# 20_-CONNECT_CONNECTORS.net
KiCad netlist of a schematic drawn in Altium Designer
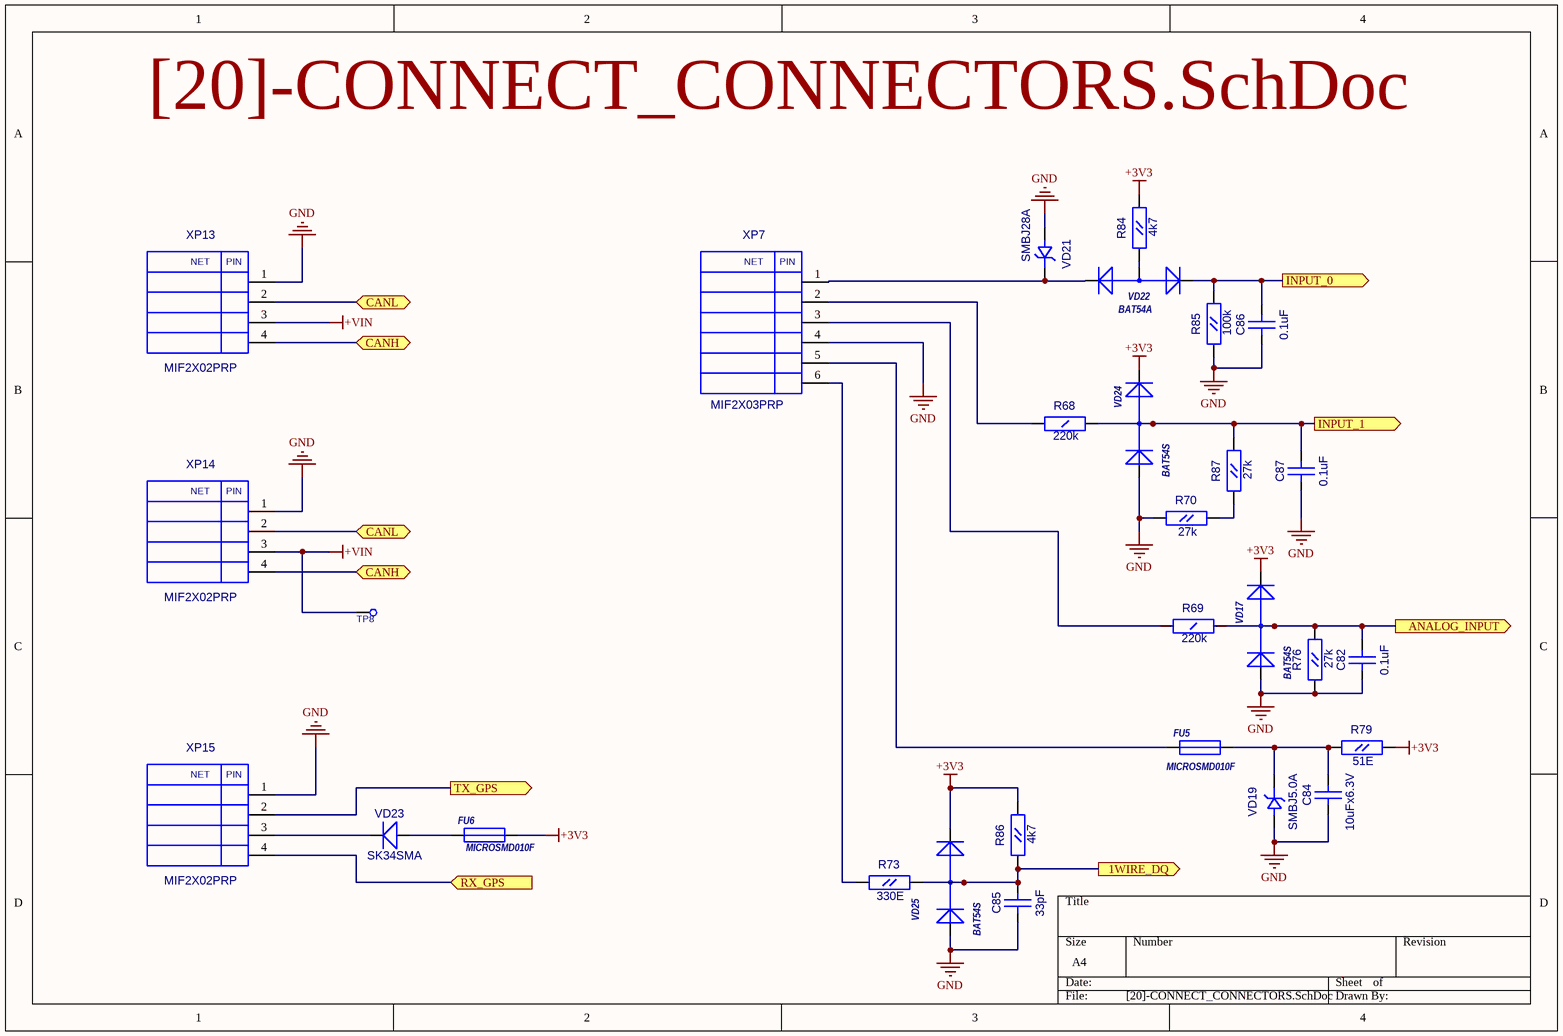
[diagram p0: [20]-CONNECT_CONNECTORS.SchDoc]

(export (version "E")
  (design (tool "Eeschema 10.0.6"))
  (components
    (comp (ref "C82")
      (value "0.1uF")
      (footprint "CC0603")
      (description "CC0603")
      (libsource (lib "gprs_modem_2") (part "CC0603"))
    )
    (comp (ref "C84")
      (value "10uFx6.3V")
      (footprint "CC0805")
      (description "CC0805")
      (libsource (lib "fizik_lib") (part "CC0805"))
    )
    (comp (ref "C85")
      (value "33pF")
      (footprint "CC0603")
      (description "CC0603")
      (libsource (lib "fizik_lib (1)") (part "CC0603"))
    )
    (comp (ref "C86")
      (value "0.1uF")
      (footprint "CC0603")
      (description "CC0603")
      (libsource (lib "fizik_lib") (part "CC0603"))
    )
    (comp (ref "C87")
      (value "0.1uF")
      (footprint "CC0603")
      (description "CC0603")
      (libsource (lib "gprs_modem_2") (part "CC0603"))
    )
    (comp (ref "FU5")
      (value "MICROSMD010F")
      (footprint "RC1210")
      (description "MICROSMD")
      (libsource (lib "fizik_lib (1)") (part "MICROSMD"))
    )
    (comp (ref "FU6")
      (value "MICROSMD010F")
      (footprint "RC1210")
      (description "MICROSMD")
      (libsource (lib "fizik_lib") (part "MICROSMD"))
    )
    (comp (ref "R68")
      (value "220k")
      (footprint "RC1206")
      (description "RC1206")
      (libsource (lib "fizik_lib") (part "RC1206"))
    )
    (comp (ref "R69")
      (value "220k")
      (footprint "RC1206")
      (description "RC1206")
      (libsource (lib "fizik_lib") (part "RC1206"))
    )
    (comp (ref "R70")
      (value "27k")
      (footprint "RC0603")
      (description "RC0603")
      (libsource (lib "fizik_lib") (part "RC0603"))
    )
    (comp (ref "R73")
      (value "330E")
      (footprint "RC0603")
      (description "RC0603")
      (libsource (lib "fizik_lib (1)") (part "RC0603"))
    )
    (comp (ref "R76")
      (value "27k")
      (footprint "RC0603")
      (description "RC0603")
      (libsource (lib "gprs_modem_2") (part "RC0603"))
    )
    (comp (ref "R79")
      (value "51E")
      (footprint "RC0603")
      (description "RC0603")
      (libsource (lib "fizik_lib (1)") (part "RC0603"))
    )
    (comp (ref "R84")
      (value "4k7")
      (footprint "RC0603")
      (description "RC0603")
      (libsource (lib "fizik_lib") (part "RC0603"))
    )
    (comp (ref "R85")
      (value "100k")
      (footprint "RC0603")
      (description "RC0603")
      (libsource (lib "fizik_lib") (part "RC0603"))
    )
    (comp (ref "R86")
      (value "4k7")
      (footprint "RC0603")
      (description "RC0603")
      (libsource (lib "fizik_lib") (part "RC0603"))
    )
    (comp (ref "R87")
      (value "27k")
      (footprint "RC0603")
      (description "RC0603")
      (libsource (lib "fizik_lib") (part "RC0603"))
    )
    (comp (ref "TP8")
      (value "TESTPOINT1")
      (footprint "TESTPOINT1")
      (libsource (lib "fizik_lib (1)") (part "TESTPOINT1"))
    )
    (comp (ref "VD17")
      (value "BAT54S")
      (footprint "SOT-23(GSD)")
      (description "1.0 Ampere General Purpose Rectifier")
      (libsource (lib "gprs_modem_2") (part "BAT54S"))
    )
    (comp (ref "VD19")
      (value "SMBJ5.0A")
      (footprint "SMB")
      (description "SMBJ")
      (libsource (lib "fizik_lib (1)") (part "SMBJ"))
    )
    (comp (ref "VD21")
      (value "SMBJ28A")
      (footprint "SMB")
      (description "SMBJ")
      (libsource (lib "fizik_lib") (part "SMBJ"))
    )
    (comp (ref "VD22")
      (value "BAT54A")
      (footprint "SOT-23(123)")
      (description "1.0 Ampere General Purpose Rectifier")
      (libsource (lib "fizik_lib") (part "BAT54A"))
    )
    (comp (ref "VD23")
      (value "SK34SMA")
      (footprint "SMA")
      (description "Schottky Rectifier")
      (libsource (lib "fizik_lib") (part "SK34SMA"))
    )
    (comp (ref "VD24")
      (value "BAT54S")
      (footprint "SOT-23(GSD)")
      (description "1.0 Ampere General Purpose Rectifier")
      (libsource (lib "fizik_lib") (part "BAT54S"))
    )
    (comp (ref "VD25")
      (value "BAT54S")
      (footprint "SOT-23(GSD)")
      (description "1.0 Ampere General Purpose Rectifier")
      (libsource (lib "fizik_lib (1)") (part "BAT54S"))
    )
    (comp (ref "XP7")
      (value "MIF2X03PRP")
      (footprint "MIF2X03PRP")
      (libsource (lib "fizik_lib (1)") (part "MIF2X03PRP"))
    )
    (comp (ref "XP13")
      (value "MIF2X02PRP")
      (footprint "MIF2X02PRP")
      (libsource (lib "fizik_lib") (part "MIF2X02PRP"))
    )
    (comp (ref "XP14")
      (value "MIF2X02PRP")
      (footprint "MIF2X02PRP")
      (libsource (lib "fizik_lib") (part "MIF2X02PRP"))
    )
    (comp (ref "XP15")
      (value "MIF2X02PRP")
      (footprint "MIF2X02PRP")
      (libsource (lib "fizik_lib") (part "MIF2X02PRP"))
    )
  )
  (nets
    (net (code "1") (name "+3V3") (class "Default")
      (node (ref "FU6") (pin "2") (pintype "passive"))
      (node (ref "R79") (pin "2") (pinfunction "B_2") (pintype "passive"))
      (node (ref "R84") (pin "2") (pinfunction "B_2") (pintype "passive"))
      (node (ref "R86") (pin "2") (pinfunction "B_2") (pintype "passive"))
      (node (ref "VD17") (pin "2") (pinfunction "K_2") (pintype "passive"))
      (node (ref "VD24") (pin "2") (pinfunction "K_2") (pintype "passive"))
      (node (ref "VD25") (pin "2") (pinfunction "K_2") (pintype "passive"))
    )
    (net (code "2") (name "+VIN") (class "Default")
      (node (ref "TP8") (pin "1") (pintype "passive"))
      (node (ref "XP13") (pin "3") (pinfunction "3_3") (pintype "passive"))
      (node (ref "XP14") (pin "3") (pinfunction "3_3") (pintype "passive"))
    )
    (net (code "3") (name "/1WIRE_DQ") (class "Default")
      (node (ref "C85") (pin "2") (pinfunction "B_2") (pintype "passive"))
      (node (ref "R73") (pin "2") (pinfunction "B_2") (pintype "passive"))
      (node (ref "R86") (pin "1") (pinfunction "A_1") (pintype "passive"))
      (node (ref "VD25") (pin "3") (pinfunction "AK_3") (pintype "passive"))
    )
    (net (code "4") (name "/ANALOG_INPUT") (class "Default")
      (node (ref "C82") (pin "2") (pinfunction "B_2") (pintype "passive"))
      (node (ref "R69") (pin "2") (pinfunction "B_2") (pintype "passive"))
      (node (ref "R76") (pin "2") (pinfunction "B_2") (pintype "passive"))
      (node (ref "VD17") (pin "3") (pinfunction "AK_3") (pintype "passive"))
    )
    (net (code "5") (name "/CANH") (class "Default")
      (node (ref "XP13") (pin "4") (pinfunction "4_4") (pintype "passive"))
      (node (ref "XP14") (pin "4") (pinfunction "4_4") (pintype "passive"))
    )
    (net (code "6") (name "/CANL") (class "Default")
      (node (ref "XP13") (pin "2") (pinfunction "2_2") (pintype "passive"))
      (node (ref "XP14") (pin "2") (pinfunction "2_2") (pintype "passive"))
    )
    (net (code "7") (name "/INPUT_0") (class "Default")
      (node (ref "C86") (pin "2") (pinfunction "B_2") (pintype "passive"))
      (node (ref "R85") (pin "2") (pinfunction "B_2") (pintype "passive"))
      (node (ref "VD22") (pin "2") (pinfunction "K_2") (pintype "passive"))
    )
    (net (code "8") (name "/INPUT_1") (class "Default")
      (node (ref "C87") (pin "2") (pinfunction "B_2") (pintype "passive"))
      (node (ref "R68") (pin "2") (pinfunction "B_2") (pintype "passive"))
      (node (ref "R87") (pin "2") (pinfunction "B_2") (pintype "passive"))
      (node (ref "VD24") (pin "3") (pinfunction "AK_3") (pintype "passive"))
    )
    (net (code "9") (name "/RX_GPS") (class "Default")
      (node (ref "XP15") (pin "4") (pinfunction "4_4") (pintype "passive"))
    )
    (net (code "10") (name "/TX_GPS") (class "Default")
      (node (ref "XP15") (pin "2") (pinfunction "2_2") (pintype "passive"))
    )
    (net (code "11") (name "GND") (class "Default")
      (node (ref "C82") (pin "1") (pinfunction "A_1") (pintype "passive"))
      (node (ref "C84") (pin "1") (pinfunction "A_1") (pintype "passive"))
      (node (ref "C85") (pin "1") (pinfunction "A_1") (pintype "passive"))
      (node (ref "C86") (pin "1") (pinfunction "A_1") (pintype "passive"))
      (node (ref "C87") (pin "1") (pinfunction "A_1") (pintype "passive"))
      (node (ref "R70") (pin "1") (pinfunction "A_1") (pintype "passive"))
      (node (ref "R76") (pin "1") (pinfunction "A_1") (pintype "passive"))
      (node (ref "R85") (pin "1") (pinfunction "A_1") (pintype "passive"))
      (node (ref "VD17") (pin "1") (pinfunction "A_1") (pintype "passive"))
      (node (ref "VD19") (pin "1") (pinfunction "A_1") (pintype "passive"))
      (node (ref "VD21") (pin "1") (pinfunction "A_1") (pintype "passive"))
      (node (ref "VD24") (pin "1") (pinfunction "A_1") (pintype "passive"))
      (node (ref "VD25") (pin "1") (pinfunction "A_1") (pintype "passive"))
      (node (ref "XP13") (pin "1") (pinfunction "1_1") (pintype "passive"))
      (node (ref "XP14") (pin "1") (pinfunction "1_1") (pintype "passive"))
      (node (ref "XP15") (pin "1") (pinfunction "1_1") (pintype "passive"))
      (node (ref "XP7") (pin "4") (pinfunction "4_4") (pintype "passive"))
    )
    (net (code "12") (name "Net-(C84-B)") (class "Default")
      (node (ref "C84") (pin "2") (pinfunction "B_2") (pintype "passive"))
      (node (ref "FU5") (pin "2") (pintype "passive"))
      (node (ref "R79") (pin "1") (pinfunction "A_1") (pintype "passive"))
      (node (ref "VD19") (pin "2") (pinfunction "K_2") (pintype "passive"))
    )
    (net (code "13") (name "Net-(FU5-Pad1)") (class "Default")
      (node (ref "FU5") (pin "1") (pintype "passive"))
      (node (ref "XP7") (pin "5") (pinfunction "5_5") (pintype "passive"))
    )
    (net (code "14") (name "Net-(R68-A)") (class "Default")
      (node (ref "R68") (pin "1") (pinfunction "A_1") (pintype "passive"))
      (node (ref "XP7") (pin "2") (pinfunction "2_2") (pintype "passive"))
    )
    (net (code "15") (name "Net-(R69-A)") (class "Default")
      (node (ref "R69") (pin "1") (pinfunction "A_1") (pintype "passive"))
      (node (ref "XP7") (pin "3") (pinfunction "3_3") (pintype "passive"))
    )
    (net (code "16") (name "Net-(R70-B)") (class "Default")
      (node (ref "R70") (pin "2") (pinfunction "B_2") (pintype "passive"))
      (node (ref "R87") (pin "1") (pinfunction "A_1") (pintype "passive"))
    )
    (net (code "17") (name "Net-(R73-A)") (class "Default")
      (node (ref "R73") (pin "1") (pinfunction "A_1") (pintype "passive"))
      (node (ref "XP7") (pin "6") (pinfunction "6_6") (pintype "passive"))
    )
    (net (code "18") (name "Net-(R84-A)") (class "Default")
      (node (ref "R84") (pin "1") (pinfunction "A_1") (pintype "passive"))
      (node (ref "VD22") (pin "3") (pinfunction "A_3") (pintype "passive"))
    )
    (net (code "19") (name "Net-(VD21-K)") (class "Default")
      (node (ref "VD21") (pin "2") (pinfunction "K_2") (pintype "passive"))
      (node (ref "VD22") (pin "1") (pinfunction "K_1") (pintype "passive"))
      (node (ref "XP7") (pin "1") (pinfunction "1_1") (pintype "passive"))
    )
    (net (code "20") (name "Net-(VD23-A)") (class "Default")
      (node (ref "FU6") (pin "1") (pintype "passive"))
      (node (ref "VD23") (pin "1") (pinfunction "A_1") (pintype "passive"))
    )
    (net (code "21") (name "Net-(VD23-K)") (class "Default")
      (node (ref "VD23") (pin "2") (pinfunction "K_2") (pintype "passive"))
      (node (ref "XP15") (pin "3") (pinfunction "3_3") (pintype "passive"))
    )
  )
)
